# gpx_extend.net
KiCad netlist of a schematic drawn in EAGLE
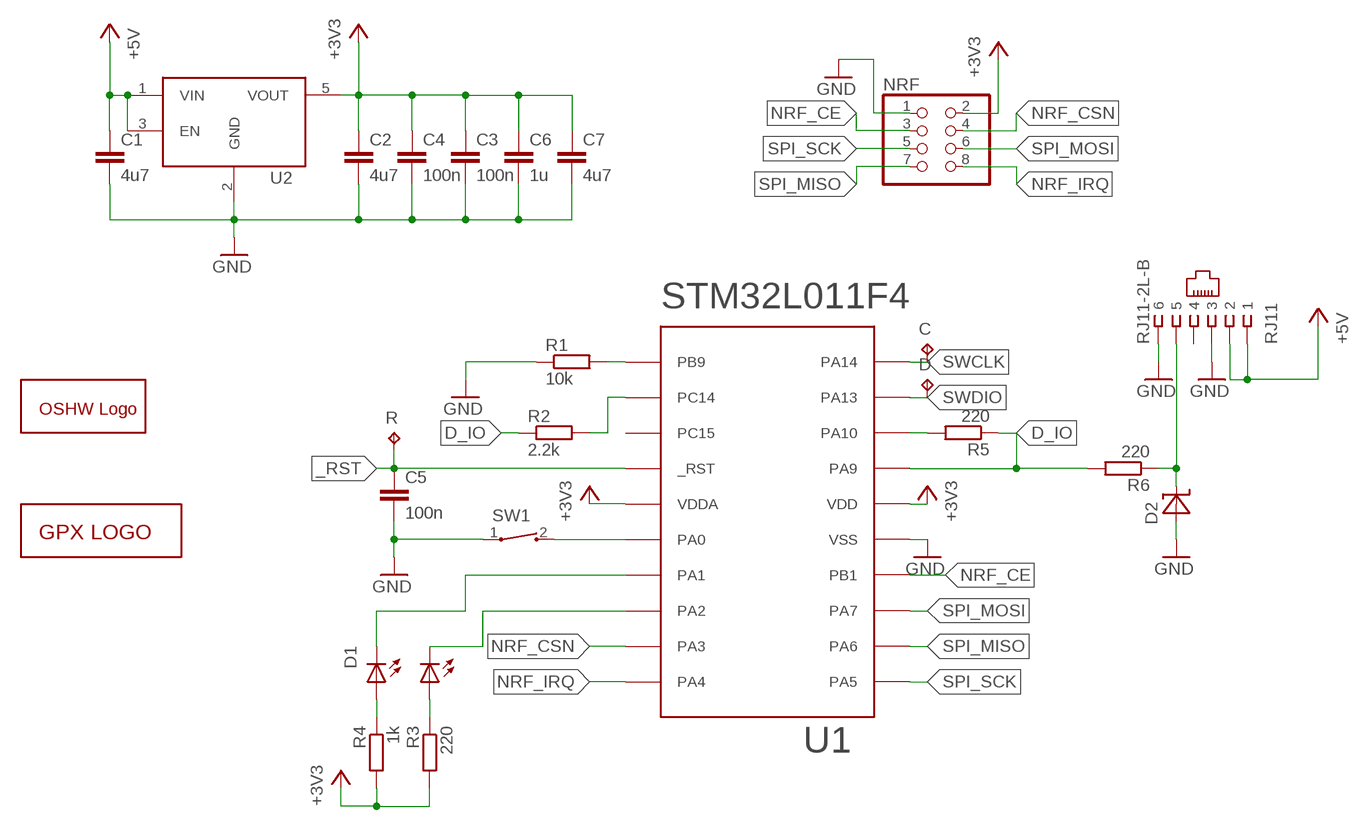
[diagram p0: schematic, sheet 1]

(export (version "E")
  (design (tool "Eeschema 10.0.6"))
  (components
    (comp (ref "C")
      (value "TPTP10R")
      (footprint "eagle-import:TP10R")
      (libsource (lib "eagle-import") (part "TPTP10R"))
    )
    (comp (ref "C1")
      (value "4u7")
      (footprint "eagle-import:0603-MMGRID")
      (libsource (lib "eagle-import") (part "C-EU-0603"))
    )
    (comp (ref "C2")
      (value "4u7")
      (footprint "eagle-import:0603-MMGRID")
      (libsource (lib "eagle-import") (part "C-EU-0603"))
    )
    (comp (ref "C3")
      (value "100n")
      (footprint "eagle-import:0603-MMGRID")
      (libsource (lib "eagle-import") (part "C-EU-0603"))
    )
    (comp (ref "C4")
      (value "100n")
      (footprint "eagle-import:0603-MMGRID")
      (libsource (lib "eagle-import") (part "C-EU-0603"))
    )
    (comp (ref "C5")
      (value "100n")
      (footprint "eagle-import:0603-MMGRID")
      (libsource (lib "eagle-import") (part "C-EU-0603"))
    )
    (comp (ref "C6")
      (value "1u")
      (footprint "eagle-import:0603-MMGRID")
      (libsource (lib "eagle-import") (part "C-EU-0603"))
    )
    (comp (ref "C7")
      (value "4u7")
      (footprint "eagle-import:0603-MMGRID")
      (libsource (lib "eagle-import") (part "C-EU-0603"))
    )
    (comp (ref "D")
      (value "TPTP10R")
      (footprint "eagle-import:TP10R")
      (libsource (lib "eagle-import") (part "TPTP10R"))
    )
    (comp (ref "D1")
      (value "LED-DUAL")
      (footprint "eagle-import:LED-1210")
      (libsource (lib "eagle-import") (part "LED-DUAL"))
    )
    (comp (ref "D2")
      (value "UCLAMP3301HSOD523")
      (footprint "eagle-import:SOD523")
      (libsource (lib "eagle-import") (part "UCLAMP3301HSOD523"))
    )
    (comp (ref "GOLD_ORB_SM1")
      (value "OSHWLOGOLOGO5MM")
      (footprint "eagle-import:OSHW_5MM")
      (libsource (lib "eagle-import") (part "OSHWLOGOLOGO5MM"))
    )
    (comp (ref "NRF")
      (value "PINHD-2X4")
      (footprint "eagle-import:2X04")
      (libsource (lib "eagle-import") (part "PINHD-2X4"))
    )
    (comp (ref "R")
      (value "TPTP10R")
      (footprint "eagle-import:TP10R")
      (libsource (lib "eagle-import") (part "TPTP10R"))
    )
    (comp (ref "R1")
      (value "10k")
      (footprint "eagle-import:0603-MMGRID")
      (libsource (lib "eagle-import") (part "R-EU-0603"))
    )
    (comp (ref "R2")
      (value "2.2k")
      (footprint "eagle-import:0603-MMGRID")
      (libsource (lib "eagle-import") (part "R-EU-0603"))
    )
    (comp (ref "R3")
      (value "220")
      (footprint "eagle-import:0603-MMGRID")
      (libsource (lib "eagle-import") (part "R-EU-0603"))
    )
    (comp (ref "R4")
      (value "1k")
      (footprint "eagle-import:0603-MMGRID")
      (libsource (lib "eagle-import") (part "R-EU-0603"))
    )
    (comp (ref "R5")
      (value "220")
      (footprint "eagle-import:0603-MMGRID")
      (libsource (lib "eagle-import") (part "R-EU-0603"))
    )
    (comp (ref "R6")
      (value "220")
      (footprint "eagle-import:0603-MMGRID")
      (libsource (lib "eagle-import") (part "R-EU-0603"))
    )
    (comp (ref "RJ11")
      (value "RJ11-2L-B")
      (footprint "eagle-import:RJ11-NO_SHIELD")
      (fields (field (name "MF") "TYCO ELECTRONICS"))
      (libsource (lib "eagle-import") (part "RJ11-2L-B"))
    )
    (comp (ref "SW1")
      (value "SW-SPST")
      (footprint "eagle-import:TL3330")
      (libsource (lib "eagle-import") (part "SW-SPST"))
    )
    (comp (ref "U$1")
      (value "GPX_LOGO")
      (footprint "eagle-import:GPX_LOGO")
      (libsource (lib "eagle-import") (part "GPX_LOGO"))
    )
    (comp (ref "U1")
      (value "STM32L011F4PX")
      (footprint "eagle-import:TSSOP-20")
      (libsource (lib "eagle-import") (part "STM32L011F4PX"))
    )
    (comp (ref "U2")
      (value "MIC550X")
      (footprint "eagle-import:SOT23-5")
      (libsource (lib "eagle-import") (part "MIC550X"))
    )
  )
  (nets
    (net (code "1") (name "+3V3") (class "Default")
      (node (ref "C2") (pin "1") (pinfunction "1_1") (pintype "passive"))
      (node (ref "C3") (pin "1") (pinfunction "1_1") (pintype "passive"))
      (node (ref "C4") (pin "1") (pinfunction "1_1") (pintype "passive"))
      (node (ref "C6") (pin "1") (pinfunction "1_1") (pintype "passive"))
      (node (ref "C7") (pin "1") (pinfunction "1_1") (pintype "passive"))
      (node (ref "NRF") (pin "2") (pinfunction "2_2") (pintype "passive"))
      (node (ref "R3") (pin "2") (pinfunction "2_2") (pintype "passive"))
      (node (ref "R4") (pin "2") (pinfunction "2_2") (pintype "passive"))
      (node (ref "U1") (pin "P$16") (pinfunction "VDD_P$16") (pintype "power_in"))
      (node (ref "U1") (pin "P$5") (pinfunction "VDDA_P$5") (pintype "power_in"))
      (node (ref "U2") (pin "5") (pinfunction "VOUT_5") (pintype "bidirectional"))
    )
    (net (code "2") (name "+5V") (class "Default")
      (node (ref "C1") (pin "1") (pinfunction "1_1") (pintype "passive"))
      (node (ref "RJ11") (pin "1") (pinfunction "1_1") (pintype "passive"))
      (node (ref "RJ11") (pin "2") (pinfunction "2_2") (pintype "passive"))
      (node (ref "U2") (pin "1") (pinfunction "VIN_1") (pintype "bidirectional"))
      (node (ref "U2") (pin "3") (pinfunction "EN_3") (pintype "bidirectional"))
    )
    (net (code "3") (name "D_IO") (class "Default")
      (node (ref "R2") (pin "1") (pinfunction "1_1") (pintype "passive"))
      (node (ref "R5") (pin "1") (pinfunction "1_1") (pintype "passive"))
      (node (ref "R6") (pin "2") (pinfunction "2_2") (pintype "passive"))
      (node (ref "U1") (pin "P$17") (pinfunction "PA9_P$17") (pintype "bidirectional"))
    )
    (net (code "4") (name "GND") (class "Default")
      (node (ref "C1") (pin "2") (pinfunction "2_2") (pintype "passive"))
      (node (ref "C2") (pin "2") (pinfunction "2_2") (pintype "passive"))
      (node (ref "C3") (pin "2") (pinfunction "2_2") (pintype "passive"))
      (node (ref "C4") (pin "2") (pinfunction "2_2") (pintype "passive"))
      (node (ref "C5") (pin "2") (pinfunction "2_2") (pintype "passive"))
      (node (ref "C6") (pin "2") (pinfunction "2_2") (pintype "passive"))
      (node (ref "C7") (pin "2") (pinfunction "2_2") (pintype "passive"))
      (node (ref "D2") (pin "A") (pinfunction "A_A") (pintype "passive"))
      (node (ref "NRF") (pin "1") (pinfunction "1_1") (pintype "passive"))
      (node (ref "R1") (pin "1") (pinfunction "1_1") (pintype "passive"))
      (node (ref "RJ11") (pin "3") (pinfunction "3_3") (pintype "passive"))
      (node (ref "RJ11") (pin "6") (pinfunction "6_6") (pintype "passive"))
      (node (ref "SW1") (pin "1") (pinfunction "1_1") (pintype "passive"))
      (node (ref "U1") (pin "P$15") (pinfunction "VSS_P$15") (pintype "power_in"))
      (node (ref "U2") (pin "2") (pinfunction "GND_2") (pintype "bidirectional"))
    )
    (net (code "5") (name "NRF_CE") (class "Default")
      (node (ref "NRF") (pin "3") (pinfunction "3_3") (pintype "passive"))
      (node (ref "U1") (pin "P$14") (pinfunction "PB1_P$14") (pintype "bidirectional"))
    )
    (net (code "6") (name "NRF_CSN") (class "Default")
      (node (ref "NRF") (pin "4") (pinfunction "4_4") (pintype "passive"))
      (node (ref "U1") (pin "P$9") (pinfunction "PA3_P$9") (pintype "bidirectional"))
    )
    (net (code "7") (name "NRF_IRQ") (class "Default")
      (node (ref "NRF") (pin "8") (pinfunction "8_8") (pintype "passive"))
      (node (ref "U1") (pin "P$10") (pinfunction "PA4_P$10") (pintype "bidirectional"))
    )
    (net (code "8") (name "Net-(D1-A0)") (class "Default")
      (node (ref "D1") (pin "2") (pinfunction "A0_2") (pintype "passive"))
      (node (ref "R3") (pin "1") (pinfunction "1_1") (pintype "passive"))
    )
    (net (code "9") (name "Net-(D1-A1)") (class "Default")
      (node (ref "D1") (pin "4") (pinfunction "A1_4") (pintype "passive"))
      (node (ref "R4") (pin "1") (pinfunction "1_1") (pintype "passive"))
    )
    (net (code "10") (name "Net-(D1-C0)") (class "Default")
      (node (ref "D1") (pin "1") (pinfunction "C0_1") (pintype "passive"))
      (node (ref "U1") (pin "P$8") (pinfunction "PA2_P$8") (pintype "bidirectional"))
    )
    (net (code "11") (name "Net-(D1-C1)") (class "Default")
      (node (ref "D1") (pin "3") (pinfunction "C1_3") (pintype "passive"))
      (node (ref "U1") (pin "P$7") (pinfunction "PA1_P$7") (pintype "bidirectional"))
    )
    (net (code "12") (name "Net-(D2-PadC)") (class "Default")
      (node (ref "D2") (pin "C") (pinfunction "C_C") (pintype "passive"))
      (node (ref "R6") (pin "1") (pinfunction "1_1") (pintype "passive"))
      (node (ref "RJ11") (pin "5") (pinfunction "5_5") (pintype "passive"))
    )
    (net (code "13") (name "Net-(U1-PA0)") (class "Default")
      (node (ref "SW1") (pin "2") (pinfunction "2_2") (pintype "passive"))
      (node (ref "U1") (pin "P$6") (pinfunction "PA0_P$6") (pintype "bidirectional"))
    )
    (net (code "14") (name "Net-(U1-PA10)") (class "Default")
      (node (ref "R5") (pin "2") (pinfunction "2_2") (pintype "passive"))
      (node (ref "U1") (pin "P$18") (pinfunction "PA10_P$18") (pintype "bidirectional"))
    )
    (net (code "15") (name "Net-(U1-PB9)") (class "Default")
      (node (ref "R1") (pin "2") (pinfunction "2_2") (pintype "passive"))
      (node (ref "U1") (pin "P$1") (pinfunction "PB9_P$1") (pintype "bidirectional"))
    )
    (net (code "16") (name "Net-(U1-PC14)") (class "Default")
      (node (ref "R2") (pin "2") (pinfunction "2_2") (pintype "passive"))
      (node (ref "U1") (pin "P$2") (pinfunction "PC14_P$2") (pintype "bidirectional"))
    )
    (net (code "17") (name "SPI_MISO") (class "Default")
      (node (ref "NRF") (pin "7") (pinfunction "7_7") (pintype "passive"))
      (node (ref "U1") (pin "P$12") (pinfunction "PA6_P$12") (pintype "bidirectional"))
    )
    (net (code "18") (name "SPI_MOSI") (class "Default")
      (node (ref "NRF") (pin "6") (pinfunction "6_6") (pintype "passive"))
      (node (ref "U1") (pin "P$13") (pinfunction "PA7_P$13") (pintype "bidirectional"))
    )
    (net (code "19") (name "SPI_SCK") (class "Default")
      (node (ref "NRF") (pin "5") (pinfunction "5_5") (pintype "passive"))
      (node (ref "U1") (pin "P$11") (pinfunction "PA5_P$11") (pintype "bidirectional"))
    )
    (net (code "20") (name "SWCLK") (class "Default")
      (node (ref "C") (pin "TP") (pinfunction "TP_TP") (pintype "input"))
      (node (ref "U1") (pin "P$20") (pinfunction "PA14_P$20") (pintype "bidirectional"))
    )
    (net (code "21") (name "SWDIO") (class "Default")
      (node (ref "D") (pin "TP") (pinfunction "TP_TP") (pintype "input"))
      (node (ref "U1") (pin "P$19") (pinfunction "PA13_P$19") (pintype "bidirectional"))
    )
    (net (code "22") (name "_RST") (class "Default")
      (node (ref "C5") (pin "1") (pinfunction "1_1") (pintype "passive"))
      (node (ref "R") (pin "TP") (pinfunction "TP_TP") (pintype "input"))
      (node (ref "U1") (pin "P$4") (pinfunction "_RST_P$4") (pintype "bidirectional"))
    )
    (net (code "23") (name "unconnected-(RJ11-Pad4)") (class "Default")
      (node (ref "RJ11") (pin "4") (pinfunction "4_4") (pintype "passive"))
    )
    (net (code "24") (name "unconnected-(U1-PC15-PadP$3)") (class "Default")
      (node (ref "U1") (pin "P$3") (pinfunction "PC15_P$3") (pintype "bidirectional"))
    )
  )
)
